# Power_Management.net
KiCad netlist of a schematic drawn in Altium Designer
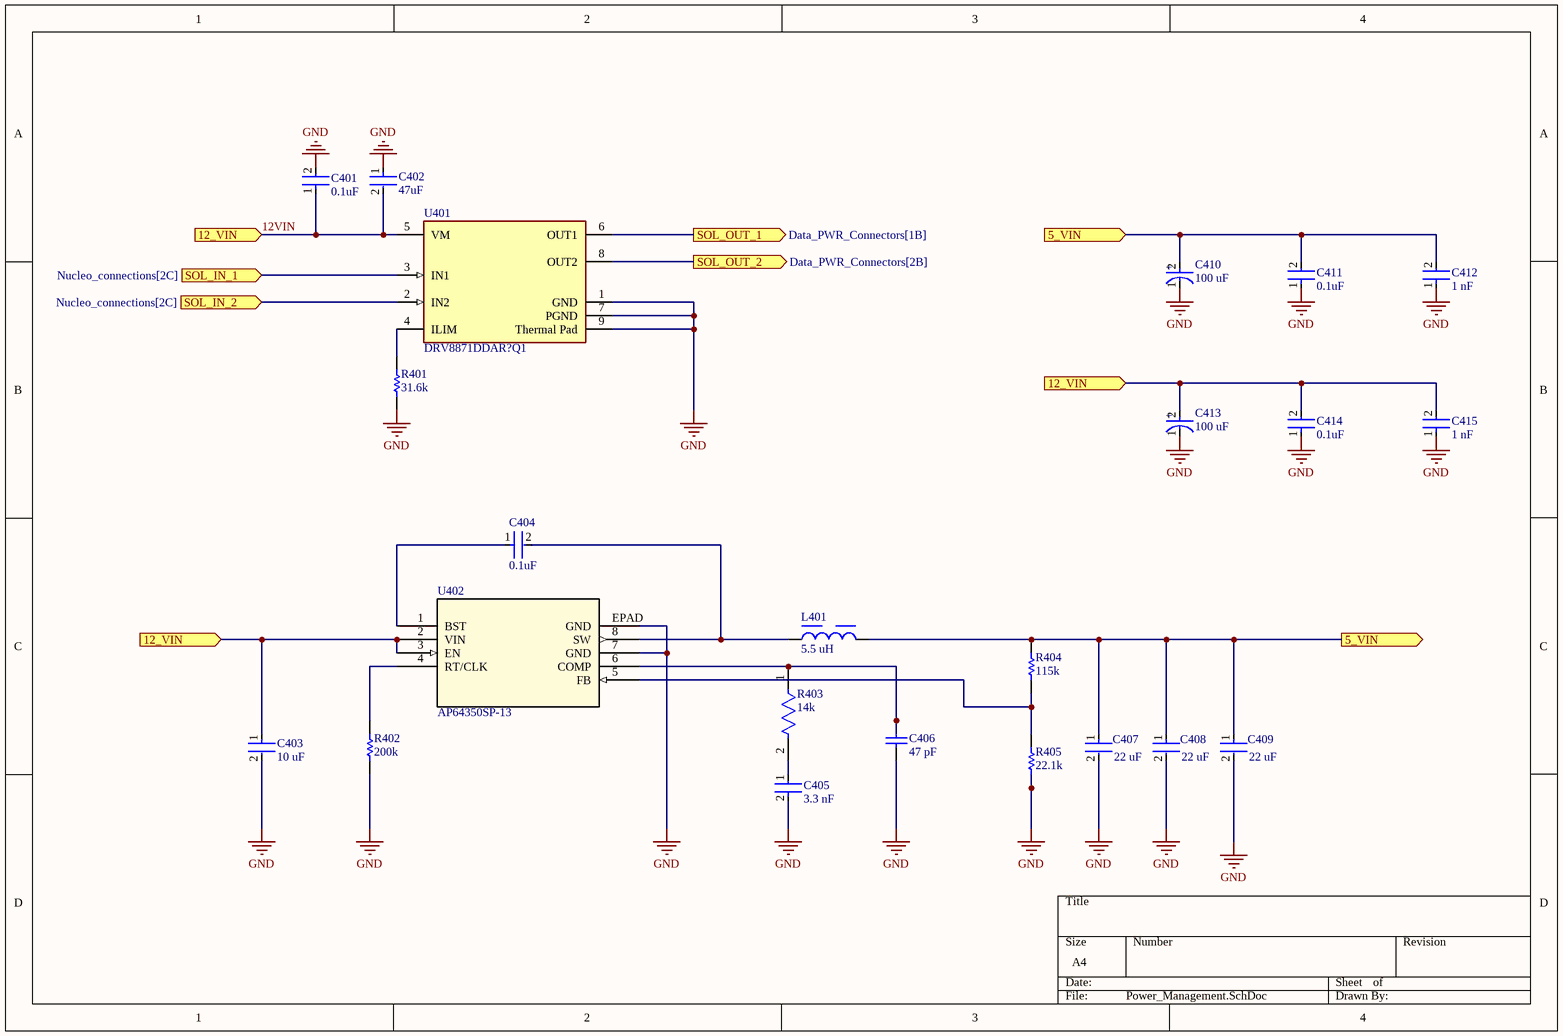
[diagram p0: Power_Management.SchDoc]

(export (version "E")
  (design (tool "Eeschema 10.0.6"))
  (components
    (comp (ref "C401")
      (value "0.1uF")
      (footprint "FP-0805-L_2_01_0_2-W_1_25-IPC_B")
      (description "Automotive Ceramic Capacitor, 0805, 100nF, 10%, X7R, 15%, 100V")
      (fields (field (name "TOLERANCE") "10%") (field (name "VOLTAGE") "100V"))
      (libsource (lib "Altium Content Vault") (part "b4654b650e69147ec39a6b967a45e02"))
    )
    (comp (ref "C402")
      (value "47uF")
      (footprint "FP-C0805C476M9PACTU-MFG")
      (description "CAP CER 47UF 6.3V X5R 0805")
      (fields (field (name "VOLTAGE") "6.3V") (field (name "TOLERANCE") "20%"))
      (libsource (lib "Altium Content Vault") (part "11868f565c42a9108669ba33697ecf6"))
    )
    (comp (ref "C403")
      (value "10 uF")
      (footprint "FP-GRM21B-0_1-IPC_C")
      (description "Chip Multilayer Ceramic Capacitors for General Purpose, 0805, 10uF, X5R, 15%, 10%, 16V")
      (fields (field (name "TOLERANCE") "10%") (field (name "VOLTAGE") "16V"))
      (libsource (lib "Altium Content Vault") (part "b4654b650e69147ec39a6b967a45e02"))
    )
    (comp (ref "C404")
      (value "0.1uF")
      (footprint "FP-0805-L_2_01_0_2-W_1_25-IPC_B")
      (description "Automotive Ceramic Capacitor, 0805, 100nF, 10%, X7R, 15%, 100V")
      (fields (field (name "TOLERANCE") "10%") (field (name "VOLTAGE") "100V"))
      (libsource (lib "Altium Content Vault") (part "b4654b650e69147ec39a6b967a45e02"))
    )
    (comp (ref "C405")
      (value "3.3 nF")
      (footprint "FP-GRM216-0_1-IPC_B")
      (description "Chip Multilayer Ceramic Capacitors for General Purpose, 0805, 3300pF, C0G, 30ppm/°C, 5%, 50V")
      (fields (field (name "VOLTAGE") "50V") (field (name "TOLERANCE") "5%"))
      (libsource (lib "Altium Content Vault") (part "236180d848d6139a670b325ea6854c9"))
    )
    (comp (ref "C406")
      (value "47 pF")
      (footprint "CAPC2013X135X50NL15T20")
      (fields (field (name "PART NUMBER") "VJ0805A470JXACW1BC") (field (name "MANUFACTURER") "Vitramon"))
      (libsource (lib "Altium Content Vault") (part "CAP"))
    )
    (comp (ref "C407")
      (value "22 uF")
      (footprint "FP-GRM21B-0_15-MFG")
      (description "Chip Multilayer Ceramic Capacitors for General Purpose, 0805, 22uF, X5R, 15%, 20%, 6.3V")
      (fields (field (name "VOLTAGE") "6.3V") (field (name "TOLERANCE") "20%"))
      (libsource (lib "Altium Content Vault") (part "b4654b650e69147ec39a6b967a45e02"))
    )
    (comp (ref "C408")
      (value "22 uF")
      (footprint "FP-GRM21B-0_15-MFG")
      (description "Chip Multilayer Ceramic Capacitors for General Purpose, 0805, 22uF, X5R, 15%, 20%, 6.3V")
      (fields (field (name "VOLTAGE") "6.3V") (field (name "TOLERANCE") "20%"))
      (libsource (lib "Altium Content Vault") (part "b4654b650e69147ec39a6b967a45e02"))
    )
    (comp (ref "C409")
      (value "22 uF")
      (footprint "FP-GRM21B-0_15-MFG")
      (description "Chip Multilayer Ceramic Capacitors for General Purpose, 0805, 22uF, X5R, 15%, 20%, 6.3V")
      (fields (field (name "VOLTAGE") "6.3V") (field (name "TOLERANCE") "20%"))
      (libsource (lib "Altium Content Vault") (part "b4654b650e69147ec39a6b967a45e02"))
    )
    (comp (ref "C410")
      (value "100 uF")
      (footprint "FP-RAD-TH-D_6_3_0_5-L_11-MFG")
      (description "Aluminum Electrolytic Capacitors (Radial Lead Type) 100uF ±20% 25V")
      (fields (field (name "TOLERANCE") "20%"))
      (libsource (lib "Altium Content Vault") (part "a00bbbee19879c290e62620ae7e47b1"))
    )
    (comp (ref "C411")
      (value "0.1uF")
      (footprint "FP-0805-L_2_01_0_2-W_1_25-IPC_B")
      (description "Automotive Ceramic Capacitor, 0805, 100nF, 10%, X7R, 15%, 100V")
      (fields (field (name "TOLERANCE") "10%") (field (name "VOLTAGE") "100V"))
      (libsource (lib "Altium Content Vault") (part "b4654b650e69147ec39a6b967a45e02"))
    )
    (comp (ref "C412")
      (value "1 nF")
      (footprint "FP-0805-L_2_01_0_2-W_1_25-IPC_C")
      (description "General Purpose Ceramic Capacitor, 0805, 1nF, 10%, X7R, 0.15, 50V")
      (fields (field (name "VOLTAGE") "50V") (field (name "TOLERANCE") "10%"))
      (libsource (lib "Altium Content Vault") (part "02cd4be3c70576c341d710602a673aa"))
    )
    (comp (ref "C413")
      (value "100 uF")
      (footprint "FP-RAD-TH-D_6_3_0_5-L_11-MFG")
      (description "Aluminum Electrolytic Capacitors (Radial Lead Type) 100uF ±20% 25V")
      (fields (field (name "TOLERANCE") "20%"))
      (libsource (lib "Altium Content Vault") (part "a00bbbee19879c290e62620ae7e47b1"))
    )
    (comp (ref "C414")
      (value "0.1uF")
      (footprint "FP-0805-L_2_01_0_2-W_1_25-IPC_B")
      (description "Automotive Ceramic Capacitor, 0805, 100nF, 10%, X7R, 15%, 100V")
      (fields (field (name "TOLERANCE") "10%") (field (name "VOLTAGE") "100V"))
      (libsource (lib "Altium Content Vault") (part "b4654b650e69147ec39a6b967a45e02"))
    )
    (comp (ref "C415")
      (value "1 nF")
      (footprint "FP-0805-L_2_01_0_2-W_1_25-IPC_C")
      (description "General Purpose Ceramic Capacitor, 0805, 1nF, 10%, X7R, 0.15, 50V")
      (fields (field (name "VOLTAGE") "50V") (field (name "TOLERANCE") "10%"))
      (libsource (lib "Altium Content Vault") (part "02cd4be3c70576c341d710602a673aa"))
    )
    (comp (ref "L401")
      (value "5.5 uH")
      (footprint "WE-HCI_1050")
      (fields (field (name "TOLERANCE") "20%"))
      (libsource (lib "Altium Content Vault") (part "Inductor - 3"))
    )
    (comp (ref "R401")
      (value "31.6k")
      (footprint "RESC2013X70X40LL20T20")
      (fields (field (name "PART NUMBER") "ERJ-6ENF3162V") (field (name "MANUFACTURER") "Panasonic"))
      (libsource (lib "Altium Content Vault") (part "RES"))
    )
    (comp (ref "R402")
      (value "200k")
      (footprint "RESC2013X70X40LL20T20")
      (fields (field (name "MANUFACTURER") "Panasonic") (field (name "PART NUMBER") "ERJ-6ENF2003V"))
      (libsource (lib "Altium Content Vault") (part "RES"))
    )
    (comp (ref "R403")
      (value "14k")
      (footprint "FP-CRCW0805-e3-MFG")
      (description "RES Thick Film, 14kΩ, 1%, 0.125W, 100ppm/°C, 0805")
      (fields (field (name "TOLERANCE") "1%"))
      (libsource (lib "Altium Content Vault") (part "1029c3af85768c4190bb7ad29bc67b5"))
    )
    (comp (ref "R404")
      (value "115k")
      (footprint "RESC2013X50X30LL20T20")
      (fields (field (name "MANUFACTURER") "Vishay Dale") (field (name "PART NUMBER") "CRCW0805115KFKEA"))
      (libsource (lib "Altium Content Vault") (part "RES"))
    )
    (comp (ref "R405")
      (value "22.1k")
      (footprint "RESC2013X70X40NL20T20")
      (fields (field (name "PART NUMBER") "ERJ-6ENF2212V") (field (name "MANUFACTURER") "Panasonic"))
      (libsource (lib "Altium Content Vault") (part "RES"))
    )
    (comp (ref "U401")
      (value "DRV8871DDAR?Q1")
      (footprint "FP-DDA0008E-IPC_B")
      (description "IC MOTOR DRVR UNIPLR 8SO PWRPAD")
      (libsource (lib "Altium Content Vault") (part "e376993584eeff15c1aa71204cd03ad"))
    )
    (comp (ref "U402")
      (value "AP64350SP-13")
      (footprint "SO-8EP_DIO")
      (description "No Description Available")
      (libsource (lib "AP64350SP-13") (part "AP64350SP-13"))
    )
  )
  (nets
    (net (code "1") (name "/5_VIN") (class "Default")
      (node (ref "C407") (pin "1") (pinfunction "1_1") (pintype "passive"))
      (node (ref "C408") (pin "1") (pinfunction "1_1") (pintype "passive"))
      (node (ref "C409") (pin "1") (pinfunction "1_1") (pintype "passive"))
      (node (ref "C410") (pin "2") (pinfunction "A_2") (pintype "passive"))
      (node (ref "C411") (pin "2") (pinfunction "2_2") (pintype "passive"))
      (node (ref "C412") (pin "2") (pinfunction "2_2") (pintype "passive"))
      (node (ref "L401") (pin "2") (pinfunction "2_2") (pintype "passive"))
      (node (ref "R404") (pin "2") (pinfunction "2_2") (pintype "passive"))
    )
    (net (code "2") (name "/12VIN") (class "Default")
      (node (ref "C401") (pin "1") (pinfunction "1_1") (pintype "passive"))
      (node (ref "C402") (pin "2") (pinfunction "2_2") (pintype "passive"))
      (node (ref "C403") (pin "1") (pinfunction "1_1") (pintype "passive"))
      (node (ref "C413") (pin "2") (pinfunction "A_2") (pintype "passive"))
      (node (ref "C414") (pin "2") (pinfunction "2_2") (pintype "passive"))
      (node (ref "C415") (pin "2") (pinfunction "2_2") (pintype "passive"))
      (node (ref "U401") (pin "5") (pinfunction "VM_5") (pintype "power_in"))
      (node (ref "U402") (pin "2") (pinfunction "VIN_2") (pintype "power_in"))
      (node (ref "U402") (pin "3") (pinfunction "EN_3") (pintype "input"))
    )
    (net (code "3") (name "/SOL_IN_1") (class "Default")
      (node (ref "U401") (pin "3") (pinfunction "IN1_3") (pintype "input"))
    )
    (net (code "4") (name "/SOL_IN_2") (class "Default")
      (node (ref "U401") (pin "2") (pinfunction "IN2_2") (pintype "input"))
    )
    (net (code "5") (name "/SOL_OUT_1") (class "Default")
      (node (ref "U401") (pin "6") (pinfunction "OUT1_6") (pintype "power_in"))
    )
    (net (code "6") (name "/SOL_OUT_2") (class "Default")
      (node (ref "U401") (pin "8") (pinfunction "OUT2_8") (pintype "power_in"))
    )
    (net (code "7") (name "GND") (class "Default")
      (node (ref "C401") (pin "2") (pinfunction "2_2") (pintype "passive"))
      (node (ref "C402") (pin "1") (pinfunction "1_1") (pintype "passive"))
      (node (ref "C403") (pin "2") (pinfunction "2_2") (pintype "passive"))
      (node (ref "C405") (pin "2") (pinfunction "2_2") (pintype "passive"))
      (node (ref "C406") (pin "1") (pinfunction "1_1") (pintype "passive"))
      (node (ref "C407") (pin "2") (pinfunction "2_2") (pintype "passive"))
      (node (ref "C408") (pin "2") (pinfunction "2_2") (pintype "passive"))
      (node (ref "C409") (pin "2") (pinfunction "2_2") (pintype "passive"))
      (node (ref "C410") (pin "1") (pinfunction "C_1") (pintype "passive"))
      (node (ref "C411") (pin "1") (pinfunction "1_1") (pintype "passive"))
      (node (ref "C412") (pin "1") (pinfunction "1_1") (pintype "passive"))
      (node (ref "C413") (pin "1") (pinfunction "C_1") (pintype "passive"))
      (node (ref "C414") (pin "1") (pinfunction "1_1") (pintype "passive"))
      (node (ref "C415") (pin "1") (pinfunction "1_1") (pintype "passive"))
      (node (ref "R401") (pin "1") (pinfunction "1_1") (pintype "passive"))
      (node (ref "R402") (pin "1") (pinfunction "1_1") (pintype "passive"))
      (node (ref "R405") (pin "1") (pinfunction "1_1") (pintype "passive"))
      (node (ref "U401") (pin "1") (pinfunction "GND_1") (pintype "power_in"))
      (node (ref "U401") (pin "7") (pinfunction "PGND_7") (pintype "power_in"))
      (node (ref "U401") (pin "9") (pinfunction "Thermal_Pad_9") (pintype "power_in"))
      (node (ref "U402") (pin "7") (pinfunction "GND_7") (pintype "power_in"))
      (node (ref "U402") (pin "EPAD") (pinfunction "GND_EPAD") (pintype "power_in"))
    )
    (net (code "8") (name "Net-(C405-Pad1)") (class "Default")
      (node (ref "C405") (pin "1") (pinfunction "1_1") (pintype "passive"))
      (node (ref "R403") (pin "2") (pinfunction "2_2") (pintype "passive"))
    )
    (net (code "9") (name "Net-(U401-ILIM)") (class "Default")
      (node (ref "R401") (pin "2") (pinfunction "2_2") (pintype "passive"))
      (node (ref "U401") (pin "4") (pinfunction "ILIM_4") (pintype "passive"))
    )
    (net (code "10") (name "Net-(U402-BST)") (class "Default")
      (node (ref "C404") (pin "1") (pinfunction "1_1") (pintype "passive"))
      (node (ref "U402") (pin "1") (pinfunction "BST_1") (pintype "power_in"))
    )
    (net (code "11") (name "Net-(U402-COMP)") (class "Default")
      (node (ref "C406") (pin "2") (pinfunction "2_2") (pintype "passive"))
      (node (ref "R403") (pin "1") (pinfunction "1_1") (pintype "passive"))
      (node (ref "U402") (pin "6") (pinfunction "COMP_6") (pintype "passive"))
    )
    (net (code "12") (name "Net-(U402-FB)") (class "Default")
      (node (ref "R404") (pin "1") (pinfunction "1_1") (pintype "passive"))
      (node (ref "R405") (pin "2") (pinfunction "2_2") (pintype "passive"))
      (node (ref "U402") (pin "5") (pinfunction "FB_5") (pintype "input"))
    )
    (net (code "13") (name "Net-(U402-RT{slash}CLK)") (class "Default")
      (node (ref "R402") (pin "2") (pinfunction "2_2") (pintype "passive"))
      (node (ref "U402") (pin "4") (pinfunction "RT/CLK_4") (pintype "passive"))
    )
    (net (code "14") (name "Net-(U402-SW)") (class "Default")
      (node (ref "C404") (pin "2") (pinfunction "2_2") (pintype "passive"))
      (node (ref "L401") (pin "1") (pinfunction "1_1") (pintype "passive"))
      (node (ref "U402") (pin "8") (pinfunction "SW_8") (pintype "output"))
    )
  )
)
